# garden_drill.net
KiCad netlist of a schematic drawn in EAGLE
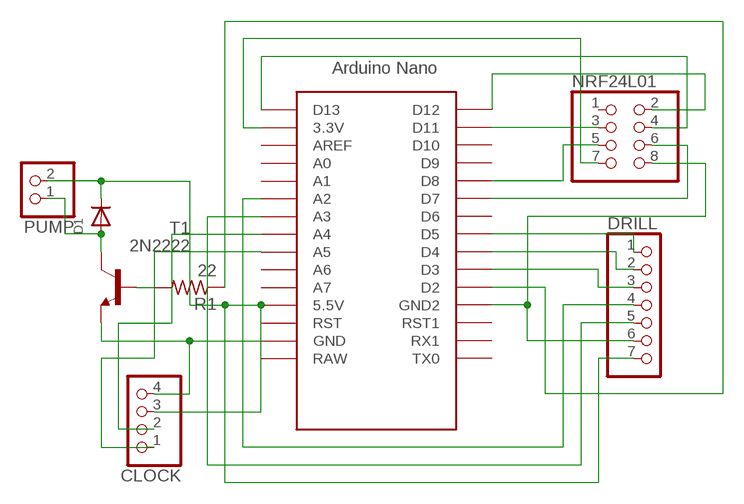
[diagram p0: schematic, sheet 1]

(export (version "E")
  (design (tool "Eeschema 10.0.6"))
  (components
    (comp (ref "CLOCK")
      (value "PINHD-1X4")
      (footprint "eagle-import:1X04")
      (libsource (lib "eagle-import") (part "PINHD-1X4"))
    )
    (comp (ref "D1")
      (value "DIODEDO-1N4148")
      (footprint "eagle-import:DO-1N4148")
      (libsource (lib "eagle-import") (part "DIODEDO-1N4148"))
    )
    (comp (ref "DRILL")
      (value "PINHD-1X7")
      (footprint "eagle-import:1X07")
      (libsource (lib "eagle-import") (part "PINHD-1X7"))
    )
    (comp (ref "NRF24L01")
      (value "PINHD-2X4_2.54")
      (footprint "eagle-import:2X04")
      (libsource (lib "eagle-import") (part "PINHD-2X4_2.54"))
    )
    (comp (ref "PUMP")
      (value "PINHD-1X2")
      (footprint "eagle-import:1X02")
      (libsource (lib "eagle-import") (part "PINHD-1X2"))
    )
    (comp (ref "R1")
      (value "22")
      (footprint "eagle-import:0204_7")
      (libsource (lib "eagle-import") (part "R-US_0204/7"))
    )
    (comp (ref "T1")
      (value "2N2222")
      (footprint "eagle-import:TO92-EBC-OVAL")
      (libsource (lib "eagle-import") (part "2N2222"))
    )
    (comp (ref "U$1")
      (value "NANO")
      (footprint "eagle-import:NANO")
      (libsource (lib "eagle-import") (part "NANO"))
    )
  )
  (nets
    (net (code "1") (name "Net-(CLOCK-Pad1)") (class "Default")
      (node (ref "CLOCK") (pin "1") (pinfunction "1_1") (pintype "passive"))
      (node (ref "U$1") (pin "A5") (pinfunction "A5_A5") (pintype "bidirectional"))
    )
    (net (code "2") (name "Net-(CLOCK-Pad2)") (class "Default")
      (node (ref "CLOCK") (pin "2") (pinfunction "2_2") (pintype "passive"))
      (node (ref "U$1") (pin "A4") (pinfunction "A4_A4") (pintype "bidirectional"))
    )
    (net (code "3") (name "Net-(CLOCK-Pad4)") (class "Default")
      (node (ref "CLOCK") (pin "4") (pinfunction "4_4") (pintype "passive"))
      (node (ref "T1") (pin "E") (pinfunction "E_E") (pintype "passive"))
      (node (ref "U$1") (pin "GND") (pinfunction "GND_GND") (pintype "bidirectional"))
    )
    (net (code "4") (name "Net-(D1-PadA)") (class "Default")
      (node (ref "D1") (pin "A") (pinfunction "A_A") (pintype "passive"))
      (node (ref "PUMP") (pin "1") (pinfunction "1_1") (pintype "passive"))
      (node (ref "T1") (pin "C") (pinfunction "C_C") (pintype "passive"))
    )
    (net (code "5") (name "Net-(DRILL-Pad1)") (class "Default")
      (node (ref "DRILL") (pin "1") (pinfunction "1_1") (pintype "passive"))
      (node (ref "U$1") (pin "D5") (pinfunction "D5_D5") (pintype "bidirectional"))
    )
    (net (code "6") (name "Net-(DRILL-Pad2)") (class "Default")
      (node (ref "DRILL") (pin "2") (pinfunction "2_2") (pintype "passive"))
      (node (ref "U$1") (pin "D4") (pinfunction "D4_D4") (pintype "bidirectional"))
    )
    (net (code "7") (name "Net-(DRILL-Pad3)") (class "Default")
      (node (ref "DRILL") (pin "3") (pinfunction "3_3") (pintype "passive"))
      (node (ref "U$1") (pin "D3") (pinfunction "D3_D3") (pintype "bidirectional"))
    )
    (net (code "8") (name "Net-(DRILL-Pad4)") (class "Default")
      (node (ref "DRILL") (pin "4") (pinfunction "4_4") (pintype "passive"))
      (node (ref "U$1") (pin "A2") (pinfunction "A2_A2") (pintype "bidirectional"))
    )
    (net (code "9") (name "Net-(DRILL-Pad5)") (class "Default")
      (node (ref "DRILL") (pin "5") (pinfunction "5_5") (pintype "passive"))
      (node (ref "U$1") (pin "A3") (pinfunction "A3_A3") (pintype "bidirectional"))
    )
    (net (code "10") (name "Net-(NRF24L01-Pad2)") (class "Default")
      (node (ref "NRF24L01") (pin "2") (pinfunction "2_2") (pintype "passive"))
      (node (ref "U$1") (pin "D12") (pinfunction "D12_D12") (pintype "bidirectional"))
    )
    (net (code "11") (name "Net-(NRF24L01-Pad3)") (class "Default")
      (node (ref "NRF24L01") (pin "3") (pinfunction "3_3") (pintype "passive"))
      (node (ref "U$1") (pin "D11") (pinfunction "D11_D11") (pintype "bidirectional"))
    )
    (net (code "12") (name "Net-(NRF24L01-Pad4)") (class "Default")
      (node (ref "NRF24L01") (pin "4") (pinfunction "4_4") (pintype "passive"))
      (node (ref "U$1") (pin "D13") (pinfunction "D13_D13") (pintype "bidirectional"))
    )
    (net (code "13") (name "Net-(NRF24L01-Pad5)") (class "Default")
      (node (ref "NRF24L01") (pin "5") (pinfunction "5_5") (pintype "passive"))
      (node (ref "U$1") (pin "D8") (pinfunction "D8_D8") (pintype "bidirectional"))
    )
    (net (code "14") (name "Net-(NRF24L01-Pad6)") (class "Default")
      (node (ref "NRF24L01") (pin "6") (pinfunction "6_6") (pintype "passive"))
      (node (ref "U$1") (pin "D7") (pinfunction "D7_D7") (pintype "bidirectional"))
    )
    (net (code "15") (name "Net-(NRF24L01-Pad7)") (class "Default")
      (node (ref "NRF24L01") (pin "7") (pinfunction "7_7") (pintype "passive"))
      (node (ref "U$1") (pin "3.3V") (pinfunction "3.3V_3.3V") (pintype "bidirectional"))
    )
    (net (code "16") (name "Net-(R1-Pad1)") (class "Default")
      (node (ref "R1") (pin "1") (pinfunction "1_1") (pintype "passive"))
      (node (ref "U$1") (pin "D2") (pinfunction "D2_D2") (pintype "bidirectional"))
    )
    (net (code "17") (name "Net-(R1-Pad2)") (class "Default")
      (node (ref "R1") (pin "2") (pinfunction "2_2") (pintype "passive"))
      (node (ref "T1") (pin "B") (pinfunction "B_B") (pintype "passive"))
    )
    (net (code "18") (name "Net-(U$1-5.5V)") (class "Default")
      (node (ref "CLOCK") (pin "3") (pinfunction "3_3") (pintype "passive"))
      (node (ref "D1") (pin "C") (pinfunction "C_C") (pintype "passive"))
      (node (ref "DRILL") (pin "7") (pinfunction "7_7") (pintype "passive"))
      (node (ref "PUMP") (pin "2") (pinfunction "2_2") (pintype "passive"))
      (node (ref "U$1") (pin "5V") (pinfunction "5.5V_5V") (pintype "bidirectional"))
    )
    (net (code "19") (name "Net-(U$1-GND2)") (class "Default")
      (node (ref "DRILL") (pin "6") (pinfunction "6_6") (pintype "passive"))
      (node (ref "NRF24L01") (pin "8") (pinfunction "8_8") (pintype "passive"))
      (node (ref "U$1") (pin "GND1") (pinfunction "GND2_GND1") (pintype "bidirectional"))
    )
    (net (code "20") (name "unconnected-(NRF24L01-Pad1)") (class "Default")
      (node (ref "NRF24L01") (pin "1") (pinfunction "1_1") (pintype "passive"))
    )
    (net (code "21") (name "unconnected-(U$1-PadA0)") (class "Default")
      (node (ref "U$1") (pin "A0") (pinfunction "A0_A0") (pintype "bidirectional"))
    )
    (net (code "22") (name "unconnected-(U$1-PadA1)") (class "Default")
      (node (ref "U$1") (pin "A1") (pinfunction "A1_A1") (pintype "bidirectional"))
    )
    (net (code "23") (name "unconnected-(U$1-PadA6)") (class "Default")
      (node (ref "U$1") (pin "A6") (pinfunction "A6_A6") (pintype "bidirectional"))
    )
    (net (code "24") (name "unconnected-(U$1-PadA7)") (class "Default")
      (node (ref "U$1") (pin "A7") (pinfunction "A7_A7") (pintype "bidirectional"))
    )
    (net (code "25") (name "unconnected-(U$1-PadAREF)") (class "Default")
      (node (ref "U$1") (pin "AREF") (pinfunction "AREF_AREF") (pintype "bidirectional"))
    )
    (net (code "26") (name "unconnected-(U$1-PadD6)") (class "Default")
      (node (ref "U$1") (pin "D6") (pinfunction "D6_D6") (pintype "bidirectional"))
    )
    (net (code "27") (name "unconnected-(U$1-PadD9)") (class "Default")
      (node (ref "U$1") (pin "D9") (pinfunction "D9_D9") (pintype "bidirectional"))
    )
    (net (code "28") (name "unconnected-(U$1-PadD10)") (class "Default")
      (node (ref "U$1") (pin "D10") (pinfunction "D10_D10") (pintype "bidirectional"))
    )
    (net (code "29") (name "unconnected-(U$1-PadICSP1)") (class "Default")
      (node (ref "U$1") (pin "ICSP1") (pinfunction "ICSP1_ICSP1") (pintype "bidirectional"))
    )
    (net (code "30") (name "unconnected-(U$1-PadICSP2)") (class "Default")
      (node (ref "U$1") (pin "ICSP2") (pinfunction "ICSP2_ICSP2") (pintype "bidirectional"))
    )
    (net (code "31") (name "unconnected-(U$1-PadICSP3)") (class "Default")
      (node (ref "U$1") (pin "ICSP3") (pinfunction "ICSP3_ICSP3") (pintype "bidirectional"))
    )
    (net (code "32") (name "unconnected-(U$1-PadICSP4)") (class "Default")
      (node (ref "U$1") (pin "ICSP4") (pinfunction "ICSP4_ICSP4") (pintype "bidirectional"))
    )
    (net (code "33") (name "unconnected-(U$1-PadICSP5)") (class "Default")
      (node (ref "U$1") (pin "ICSP5") (pinfunction "ICSP5_ICSP5") (pintype "bidirectional"))
    )
    (net (code "34") (name "unconnected-(U$1-PadICSP6)") (class "Default")
      (node (ref "U$1") (pin "ICSP6") (pinfunction "ICSP6_ICSP6") (pintype "bidirectional"))
    )
    (net (code "35") (name "unconnected-(U$1-PadRAW)") (class "Default")
      (node (ref "U$1") (pin "RAW") (pinfunction "RAW_RAW") (pintype "bidirectional"))
    )
    (net (code "36") (name "unconnected-(U$1-PadRST)") (class "Default")
      (node (ref "U$1") (pin "RST") (pinfunction "RST_RST") (pintype "bidirectional"))
    )
    (net (code "37") (name "unconnected-(U$1-PadRST1)") (class "Default")
      (node (ref "U$1") (pin "RST1") (pinfunction "RST1_RST1") (pintype "bidirectional"))
    )
    (net (code "38") (name "unconnected-(U$1-PadRX1)") (class "Default")
      (node (ref "U$1") (pin "RX1") (pinfunction "RX1_RX1") (pintype "bidirectional"))
    )
    (net (code "39") (name "unconnected-(U$1-PadTX0)") (class "Default")
      (node (ref "U$1") (pin "TX0") (pinfunction "TX0_TX0") (pintype "bidirectional"))
    )
  )
)
